# 2DDR3L_16bits.net
KiCad netlist of a schematic drawn in Altium Designer
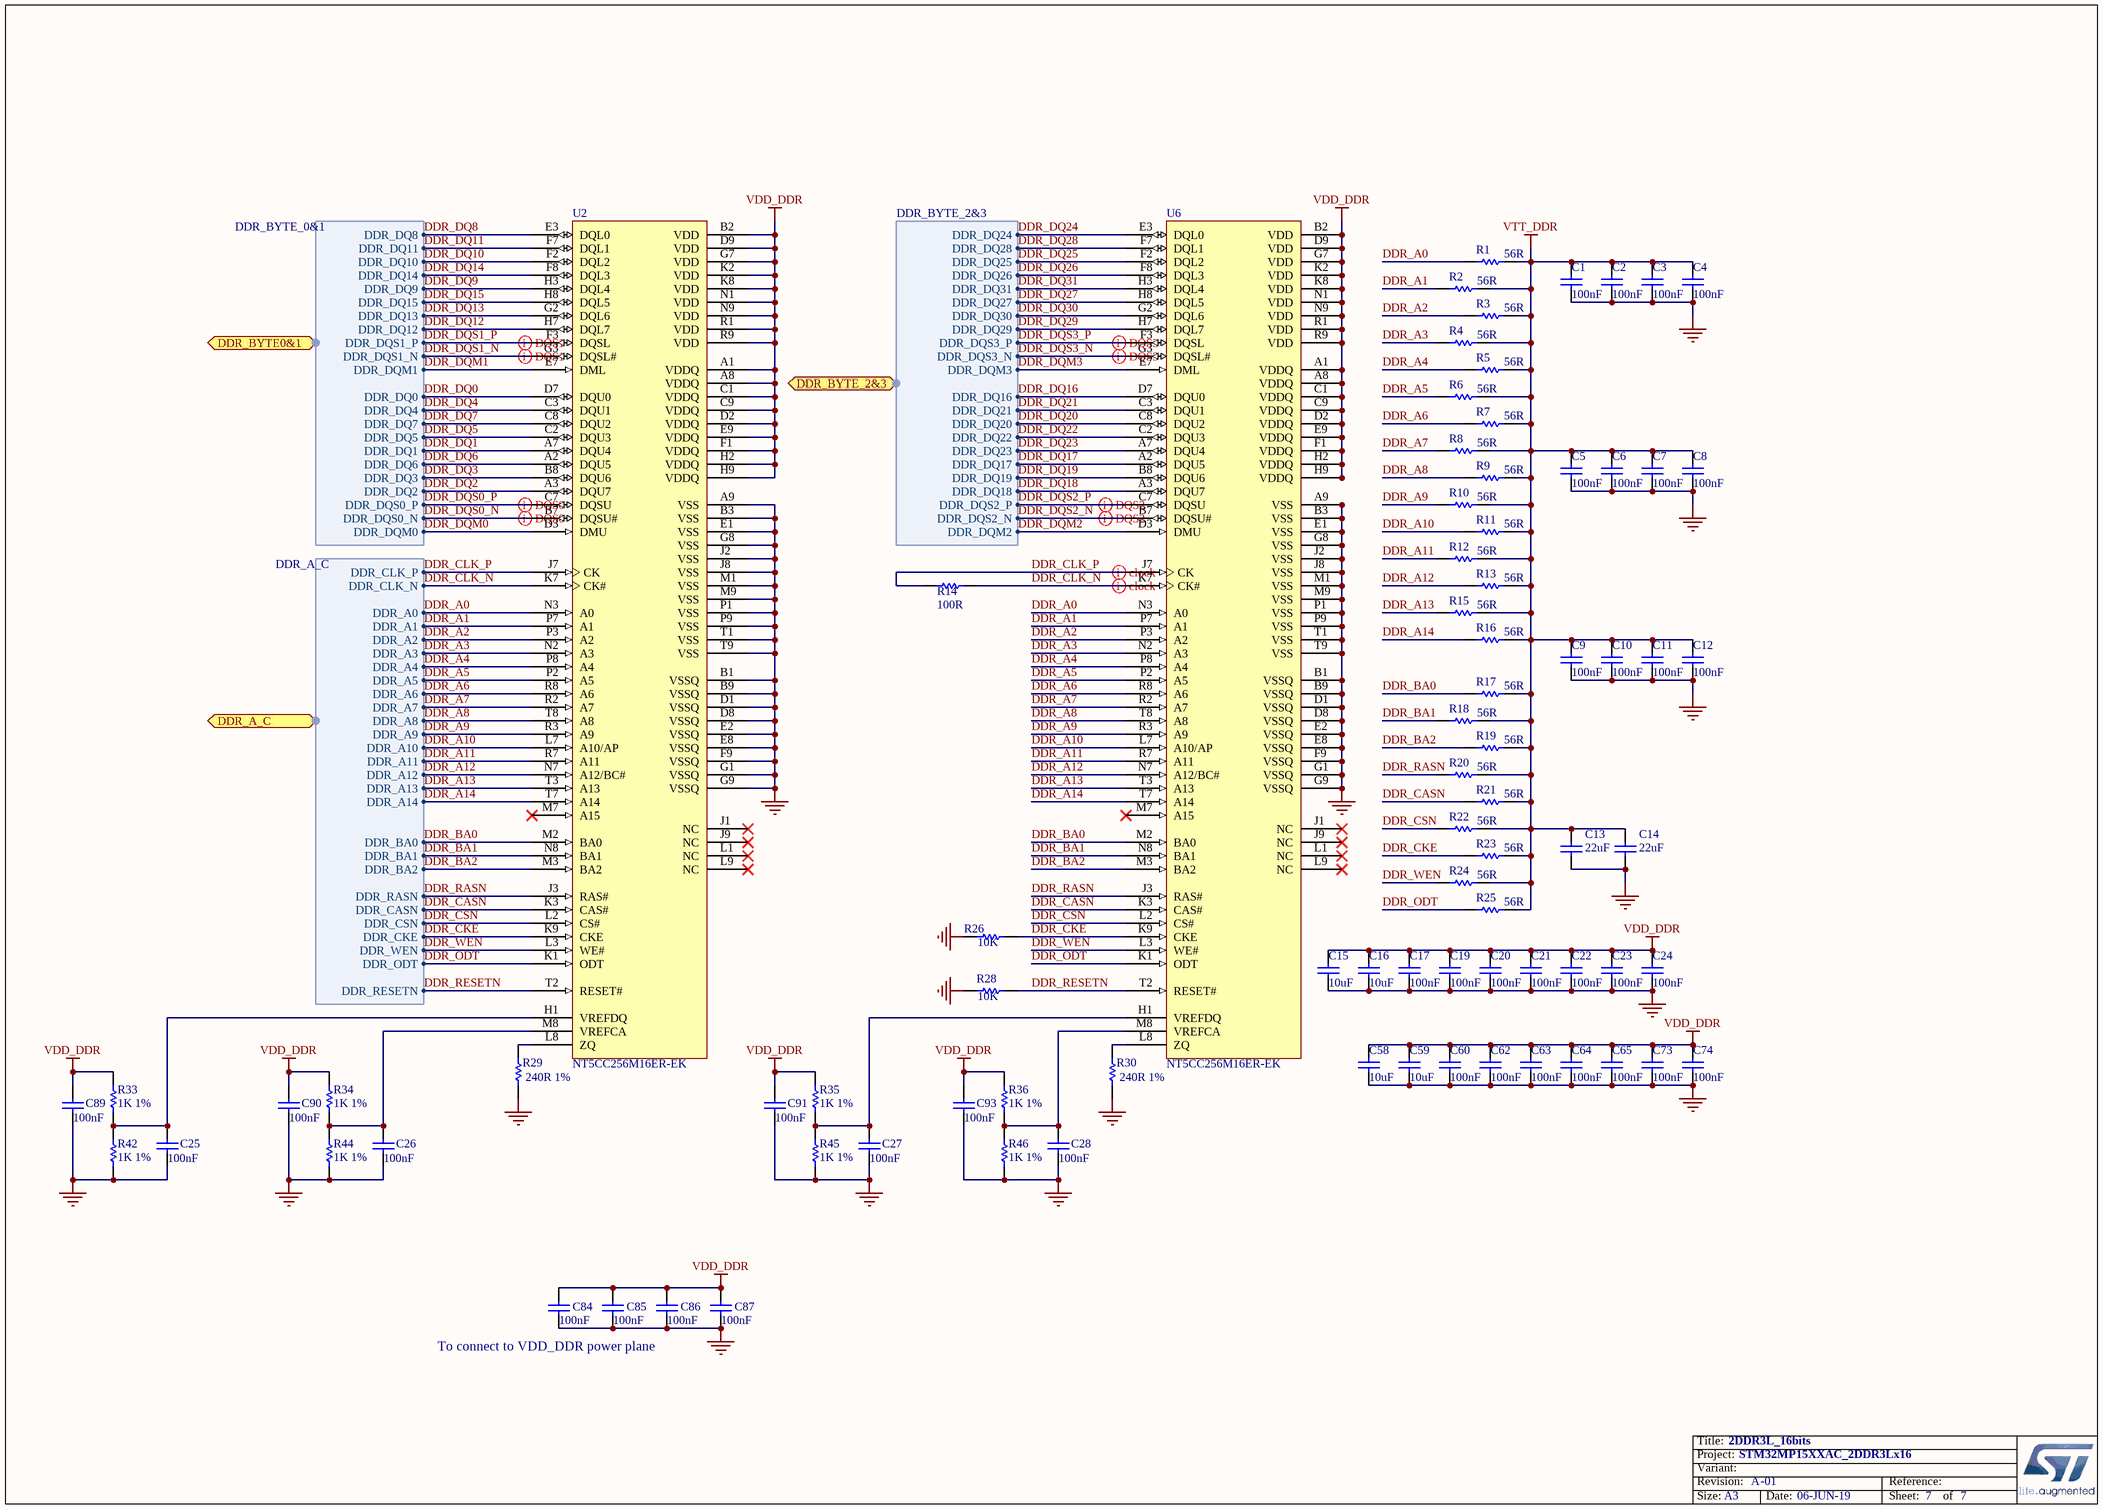
[diagram p0: 2DDR3L_16bits.SchDoc]

(export (version "E")
  (design (tool "Eeschema 10.0.6"))
  (components
    (comp (ref "C1")
      (value "100nF")
      (footprint "C0402")
      (description "Capacitor, MLCC, 100nF, 16V, X7R, 10%, 0402, T=0.5mm")
      (fields
        (field (name "INTERNAL_PART_NUMBER") "MCD-00006")
        (field (name "MANUFACTURER_PART_NUMBER") "CC0402KRX7R7BB104")
        (field (name "PROVIDED_BY") "SUBCO")
      )
      (libsource (lib "MCD_PARTS_database") (part "Capacitor"))
    )
    (comp (ref "C2")
      (value "100nF")
      (footprint "C0402")
      (description "Capacitor, MLCC, 100nF, 16V, X7R, 10%, 0402, T=0.5mm")
      (fields
        (field (name "INTERNAL_PART_NUMBER") "MCD-00006")
        (field (name "MANUFACTURER_PART_NUMBER") "CC0402KRX7R7BB104")
        (field (name "PROVIDED_BY") "SUBCO")
      )
      (libsource (lib "MCD_PARTS_database") (part "Capacitor"))
    )
    (comp (ref "C3")
      (value "100nF")
      (footprint "C0402")
      (description "Capacitor, MLCC, 100nF, 16V, X7R, 10%, 0402, T=0.5mm")
      (fields
        (field (name "INTERNAL_PART_NUMBER") "MCD-00006")
        (field (name "MANUFACTURER_PART_NUMBER") "CC0402KRX7R7BB104")
        (field (name "PROVIDED_BY") "SUBCO")
      )
      (libsource (lib "MCD_PARTS_database") (part "Capacitor"))
    )
    (comp (ref "C4")
      (value "100nF")
      (footprint "C0402")
      (description "Capacitor, MLCC, 100nF, 16V, X7R, 10%, 0402, T=0.5mm")
      (fields
        (field (name "INTERNAL_PART_NUMBER") "MCD-00006")
        (field (name "MANUFACTURER_PART_NUMBER") "CC0402KRX7R7BB104")
        (field (name "PROVIDED_BY") "SUBCO")
      )
      (libsource (lib "MCD_PARTS_database") (part "Capacitor"))
    )
    (comp (ref "C5")
      (value "100nF")
      (footprint "C0402")
      (description "Capacitor, MLCC, 100nF, 16V, X7R, 10%, 0402, T=0.5mm")
      (fields
        (field (name "INTERNAL_PART_NUMBER") "MCD-00006")
        (field (name "MANUFACTURER_PART_NUMBER") "CC0402KRX7R7BB104")
        (field (name "PROVIDED_BY") "SUBCO")
      )
      (libsource (lib "MCD_PARTS_database") (part "Capacitor"))
    )
    (comp (ref "C6")
      (value "100nF")
      (footprint "C0402")
      (description "Capacitor, MLCC, 100nF, 16V, X7R, 10%, 0402, T=0.5mm")
      (fields
        (field (name "INTERNAL_PART_NUMBER") "MCD-00006")
        (field (name "MANUFACTURER_PART_NUMBER") "CC0402KRX7R7BB104")
        (field (name "PROVIDED_BY") "SUBCO")
      )
      (libsource (lib "MCD_PARTS_database") (part "Capacitor"))
    )
    (comp (ref "C7")
      (value "100nF")
      (footprint "C0402")
      (description "Capacitor, MLCC, 100nF, 16V, X7R, 10%, 0402, T=0.5mm")
      (fields
        (field (name "INTERNAL_PART_NUMBER") "MCD-00006")
        (field (name "MANUFACTURER_PART_NUMBER") "CC0402KRX7R7BB104")
        (field (name "PROVIDED_BY") "SUBCO")
      )
      (libsource (lib "MCD_PARTS_database") (part "Capacitor"))
    )
    (comp (ref "C8")
      (value "100nF")
      (footprint "C0402")
      (description "Capacitor, MLCC, 100nF, 16V, X7R, 10%, 0402, T=0.5mm")
      (fields
        (field (name "INTERNAL_PART_NUMBER") "MCD-00006")
        (field (name "MANUFACTURER_PART_NUMBER") "CC0402KRX7R7BB104")
        (field (name "PROVIDED_BY") "SUBCO")
      )
      (libsource (lib "MCD_PARTS_database") (part "Capacitor"))
    )
    (comp (ref "C9")
      (value "100nF")
      (footprint "C0402")
      (description "Capacitor, MLCC, 100nF, 16V, X7R, 10%, 0402, T=0.5mm")
      (fields
        (field (name "INTERNAL_PART_NUMBER") "MCD-00006")
        (field (name "MANUFACTURER_PART_NUMBER") "CC0402KRX7R7BB104")
        (field (name "PROVIDED_BY") "SUBCO")
      )
      (libsource (lib "MCD_PARTS_database") (part "Capacitor"))
    )
    (comp (ref "C10")
      (value "100nF")
      (footprint "C0402")
      (description "Capacitor, MLCC, 100nF, 16V, X7R, 10%, 0402, T=0.5mm")
      (fields
        (field (name "INTERNAL_PART_NUMBER") "MCD-00006")
        (field (name "MANUFACTURER_PART_NUMBER") "CC0402KRX7R7BB104")
        (field (name "PROVIDED_BY") "SUBCO")
      )
      (libsource (lib "MCD_PARTS_database") (part "Capacitor"))
    )
    (comp (ref "C11")
      (value "100nF")
      (footprint "C0402")
      (description "Capacitor, MLCC, 100nF, 16V, X7R, 10%, 0402, T=0.5mm")
      (fields
        (field (name "INTERNAL_PART_NUMBER") "MCD-00006")
        (field (name "MANUFACTURER_PART_NUMBER") "CC0402KRX7R7BB104")
        (field (name "PROVIDED_BY") "SUBCO")
      )
      (libsource (lib "MCD_PARTS_database") (part "Capacitor"))
    )
    (comp (ref "C12")
      (value "100nF")
      (footprint "C0402")
      (description "Capacitor, MLCC, 100nF, 16V, X7R, 10%, 0402, T=0.5mm")
      (fields
        (field (name "INTERNAL_PART_NUMBER") "MCD-00006")
        (field (name "MANUFACTURER_PART_NUMBER") "CC0402KRX7R7BB104")
        (field (name "PROVIDED_BY") "SUBCO")
      )
      (libsource (lib "MCD_PARTS_database") (part "Capacitor"))
    )
    (comp (ref "C13")
      (value "22uF")
      (footprint "C0603")
      (description "Capacitor, MLCC, 22uF, 6V3, X5R, 20%, 0603, T=0,8mm")
      (fields
        (field (name "INTERNAL_PART_NUMBER") "MCD-00100")
        (field (name "MANUFACTURER_PART_NUMBER") "GRM188R60J226MEA0J")
        (field (name "PROVIDED_BY") "SUBCO")
      )
      (libsource (lib "MCD_PARTS_database") (part "Capacitor"))
    )
    (comp (ref "C14")
      (value "22uF")
      (footprint "C0603")
      (description "Capacitor, MLCC, 22uF, 6V3, X5R, 20%, 0603, T=0,8mm")
      (fields
        (field (name "INTERNAL_PART_NUMBER") "MCD-00100")
        (field (name "MANUFACTURER_PART_NUMBER") "GRM188R60J226MEA0J")
        (field (name "PROVIDED_BY") "SUBCO")
      )
      (libsource (lib "MCD_PARTS_database") (part "Capacitor"))
    )
    (comp (ref "C15")
      (value "10uF")
      (footprint "C0603")
      (description "Capacitor, MLCC, 10µF, 10V, X5R, 10%, 0603, T=0.8mm")
      (fields
        (field (name "INTERNAL_PART_NUMBER") "MCD-01124")
        (field (name "MANUFACTURER_PART_NUMBER") "GRM188R61A106KAAL")
        (field (name "PROVIDED_BY") "SUBCO")
      )
      (libsource (lib "MCD_PARTS_database") (part "Capacitor"))
    )
    (comp (ref "C16")
      (value "10uF")
      (footprint "C0603")
      (description "Capacitor, MLCC, 10µF, 10V, X5R, 10%, 0603, T=0.8mm")
      (fields
        (field (name "INTERNAL_PART_NUMBER") "MCD-01124")
        (field (name "MANUFACTURER_PART_NUMBER") "GRM188R61A106KAAL")
        (field (name "PROVIDED_BY") "SUBCO")
      )
      (libsource (lib "MCD_PARTS_database") (part "Capacitor"))
    )
    (comp (ref "C17")
      (value "100nF")
      (footprint "C0402")
      (description "Capacitor, MLCC, 100nF, 16V, X7R, 10%, 0402, T=0.5mm")
      (fields
        (field (name "INTERNAL_PART_NUMBER") "MCD-00006")
        (field (name "MANUFACTURER_PART_NUMBER") "CC0402KRX7R7BB104")
        (field (name "PROVIDED_BY") "SUBCO")
      )
      (libsource (lib "MCD_PARTS_database") (part "Capacitor"))
    )
    (comp (ref "C19")
      (value "100nF")
      (footprint "C0402")
      (description "Capacitor, MLCC, 100nF, 16V, X7R, 10%, 0402, T=0.5mm")
      (fields
        (field (name "INTERNAL_PART_NUMBER") "MCD-00006")
        (field (name "MANUFACTURER_PART_NUMBER") "CC0402KRX7R7BB104")
        (field (name "PROVIDED_BY") "SUBCO")
      )
      (libsource (lib "MCD_PARTS_database") (part "Capacitor"))
    )
    (comp (ref "C20")
      (value "100nF")
      (footprint "C0402")
      (description "Capacitor, MLCC, 100nF, 16V, X7R, 10%, 0402, T=0.5mm")
      (fields
        (field (name "INTERNAL_PART_NUMBER") "MCD-00006")
        (field (name "MANUFACTURER_PART_NUMBER") "CC0402KRX7R7BB104")
        (field (name "PROVIDED_BY") "SUBCO")
      )
      (libsource (lib "MCD_PARTS_database") (part "Capacitor"))
    )
    (comp (ref "C21")
      (value "100nF")
      (footprint "C0402")
      (description "Capacitor, MLCC, 100nF, 16V, X7R, 10%, 0402, T=0.5mm")
      (fields
        (field (name "INTERNAL_PART_NUMBER") "MCD-00006")
        (field (name "MANUFACTURER_PART_NUMBER") "CC0402KRX7R7BB104")
        (field (name "PROVIDED_BY") "SUBCO")
      )
      (libsource (lib "MCD_PARTS_database") (part "Capacitor"))
    )
    (comp (ref "C22")
      (value "100nF")
      (footprint "C0402")
      (description "Capacitor, MLCC, 100nF, 16V, X7R, 10%, 0402, T=0.5mm")
      (fields
        (field (name "INTERNAL_PART_NUMBER") "MCD-00006")
        (field (name "MANUFACTURER_PART_NUMBER") "CC0402KRX7R7BB104")
        (field (name "PROVIDED_BY") "SUBCO")
      )
      (libsource (lib "MCD_PARTS_database") (part "Capacitor"))
    )
    (comp (ref "C23")
      (value "100nF")
      (footprint "C0402")
      (description "Capacitor, MLCC, 100nF, 16V, X7R, 10%, 0402, T=0.5mm")
      (fields
        (field (name "INTERNAL_PART_NUMBER") "MCD-00006")
        (field (name "MANUFACTURER_PART_NUMBER") "CC0402KRX7R7BB104")
        (field (name "PROVIDED_BY") "SUBCO")
      )
      (libsource (lib "MCD_PARTS_database") (part "Capacitor"))
    )
    (comp (ref "C24")
      (value "100nF")
      (footprint "C0402")
      (description "Capacitor, MLCC, 100nF, 16V, X7R, 10%, 0402, T=0.5mm")
      (fields
        (field (name "INTERNAL_PART_NUMBER") "MCD-00006")
        (field (name "MANUFACTURER_PART_NUMBER") "CC0402KRX7R7BB104")
        (field (name "PROVIDED_BY") "SUBCO")
      )
      (libsource (lib "MCD_PARTS_database") (part "Capacitor"))
    )
    (comp (ref "C25")
      (value "100nF")
      (footprint "C0402")
      (description "Capacitor, MLCC, 100nF, 16V, X7R, 10%, 0402, T=0.5mm")
      (fields
        (field (name "INTERNAL_PART_NUMBER") "MCD-00006")
        (field (name "MANUFACTURER_PART_NUMBER") "CC0402KRX7R7BB104")
        (field (name "PROVIDED_BY") "SUBCO")
      )
      (libsource (lib "MCD_PARTS_database") (part "Capacitor"))
    )
    (comp (ref "C26")
      (value "100nF")
      (footprint "C0402")
      (description "Capacitor, MLCC, 100nF, 16V, X7R, 10%, 0402, T=0.5mm")
      (fields
        (field (name "INTERNAL_PART_NUMBER") "MCD-00006")
        (field (name "MANUFACTURER_PART_NUMBER") "CC0402KRX7R7BB104")
        (field (name "PROVIDED_BY") "SUBCO")
      )
      (libsource (lib "MCD_PARTS_database") (part "Capacitor"))
    )
    (comp (ref "C27")
      (value "100nF")
      (footprint "C0402")
      (description "Capacitor, MLCC, 100nF, 16V, X7R, 10%, 0402, T=0.5mm")
      (fields
        (field (name "INTERNAL_PART_NUMBER") "MCD-00006")
        (field (name "MANUFACTURER_PART_NUMBER") "CC0402KRX7R7BB104")
        (field (name "PROVIDED_BY") "SUBCO")
      )
      (libsource (lib "MCD_PARTS_database") (part "Capacitor"))
    )
    (comp (ref "C28")
      (value "100nF")
      (footprint "C0402")
      (description "Capacitor, MLCC, 100nF, 16V, X7R, 10%, 0402, T=0.5mm")
      (fields
        (field (name "INTERNAL_PART_NUMBER") "MCD-00006")
        (field (name "MANUFACTURER_PART_NUMBER") "CC0402KRX7R7BB104")
        (field (name "PROVIDED_BY") "SUBCO")
      )
      (libsource (lib "MCD_PARTS_database") (part "Capacitor"))
    )
    (comp (ref "C58")
      (value "10uF")
      (footprint "C0603")
      (description "Capacitor, MLCC, 10µF, 10V, X5R, 10%, 0603, T=0.8mm")
      (fields
        (field (name "INTERNAL_PART_NUMBER") "MCD-01124")
        (field (name "MANUFACTURER_PART_NUMBER") "GRM188R61A106KAAL")
        (field (name "PROVIDED_BY") "SUBCO")
      )
      (libsource (lib "MCD_PARTS_database") (part "Capacitor"))
    )
    (comp (ref "C59")
      (value "10uF")
      (footprint "C0603")
      (description "Capacitor, MLCC, 10µF, 10V, X5R, 10%, 0603, T=0.8mm")
      (fields
        (field (name "INTERNAL_PART_NUMBER") "MCD-01124")
        (field (name "MANUFACTURER_PART_NUMBER") "GRM188R61A106KAAL")
        (field (name "PROVIDED_BY") "SUBCO")
      )
      (libsource (lib "MCD_PARTS_database") (part "Capacitor"))
    )
    (comp (ref "C60")
      (value "100nF")
      (footprint "C0402")
      (description "Capacitor, MLCC, 100nF, 16V, X7R, 10%, 0402, T=0.5mm")
      (fields
        (field (name "INTERNAL_PART_NUMBER") "MCD-00006")
        (field (name "MANUFACTURER_PART_NUMBER") "CC0402KRX7R7BB104")
        (field (name "PROVIDED_BY") "SUBCO")
      )
      (libsource (lib "MCD_PARTS_database") (part "Capacitor"))
    )
    (comp (ref "C62")
      (value "100nF")
      (footprint "C0402")
      (description "Capacitor, MLCC, 100nF, 16V, X7R, 10%, 0402, T=0.5mm")
      (fields
        (field (name "INTERNAL_PART_NUMBER") "MCD-00006")
        (field (name "MANUFACTURER_PART_NUMBER") "CC0402KRX7R7BB104")
        (field (name "PROVIDED_BY") "SUBCO")
      )
      (libsource (lib "MCD_PARTS_database") (part "Capacitor"))
    )
    (comp (ref "C63")
      (value "100nF")
      (footprint "C0402")
      (description "Capacitor, MLCC, 100nF, 16V, X7R, 10%, 0402, T=0.5mm")
      (fields
        (field (name "INTERNAL_PART_NUMBER") "MCD-00006")
        (field (name "MANUFACTURER_PART_NUMBER") "CC0402KRX7R7BB104")
        (field (name "PROVIDED_BY") "SUBCO")
      )
      (libsource (lib "MCD_PARTS_database") (part "Capacitor"))
    )
    (comp (ref "C64")
      (value "100nF")
      (footprint "C0402")
      (description "Capacitor, MLCC, 100nF, 16V, X7R, 10%, 0402, T=0.5mm")
      (fields
        (field (name "INTERNAL_PART_NUMBER") "MCD-00006")
        (field (name "MANUFACTURER_PART_NUMBER") "CC0402KRX7R7BB104")
        (field (name "PROVIDED_BY") "SUBCO")
      )
      (libsource (lib "MCD_PARTS_database") (part "Capacitor"))
    )
    (comp (ref "C65")
      (value "100nF")
      (footprint "C0402")
      (description "Capacitor, MLCC, 100nF, 16V, X7R, 10%, 0402, T=0.5mm")
      (fields
        (field (name "INTERNAL_PART_NUMBER") "MCD-00006")
        (field (name "MANUFACTURER_PART_NUMBER") "CC0402KRX7R7BB104")
        (field (name "PROVIDED_BY") "SUBCO")
      )
      (libsource (lib "MCD_PARTS_database") (part "Capacitor"))
    )
    (comp (ref "C73")
      (value "100nF")
      (footprint "C0402")
      (description "Capacitor, MLCC, 100nF, 16V, X7R, 10%, 0402, T=0.5mm")
      (fields
        (field (name "INTERNAL_PART_NUMBER") "MCD-00006")
        (field (name "MANUFACTURER_PART_NUMBER") "CC0402KRX7R7BB104")
        (field (name "PROVIDED_BY") "SUBCO")
      )
      (libsource (lib "MCD_PARTS_database") (part "Capacitor"))
    )
    (comp (ref "C74")
      (value "100nF")
      (footprint "C0402")
      (description "Capacitor, MLCC, 100nF, 16V, X7R, 10%, 0402, T=0.5mm")
      (fields
        (field (name "INTERNAL_PART_NUMBER") "MCD-00006")
        (field (name "MANUFACTURER_PART_NUMBER") "CC0402KRX7R7BB104")
        (field (name "PROVIDED_BY") "SUBCO")
      )
      (libsource (lib "MCD_PARTS_database") (part "Capacitor"))
    )
    (comp (ref "C84")
      (value "100nF")
      (footprint "C0402")
      (description "Capacitor, MLCC, 100nF, 16V, X7R, 10%, 0402, T=0.5mm")
      (fields
        (field (name "INTERNAL_PART_NUMBER") "MCD-00006")
        (field (name "MANUFACTURER_PART_NUMBER") "CC0402KRX7R7BB104")
        (field (name "PROVIDED_BY") "SUBCO")
      )
      (libsource (lib "MCD_PARTS_database") (part "Capacitor"))
    )
    (comp (ref "C85")
      (value "100nF")
      (footprint "C0402")
      (description "Capacitor, MLCC, 100nF, 16V, X7R, 10%, 0402, T=0.5mm")
      (fields
        (field (name "INTERNAL_PART_NUMBER") "MCD-00006")
        (field (name "MANUFACTURER_PART_NUMBER") "CC0402KRX7R7BB104")
        (field (name "PROVIDED_BY") "SUBCO")
      )
      (libsource (lib "MCD_PARTS_database") (part "Capacitor"))
    )
    (comp (ref "C86")
      (value "100nF")
      (footprint "C0402")
      (description "Capacitor, MLCC, 100nF, 16V, X7R, 10%, 0402, T=0.5mm")
      (fields
        (field (name "INTERNAL_PART_NUMBER") "MCD-00006")
        (field (name "MANUFACTURER_PART_NUMBER") "CC0402KRX7R7BB104")
        (field (name "PROVIDED_BY") "SUBCO")
      )
      (libsource (lib "MCD_PARTS_database") (part "Capacitor"))
    )
    (comp (ref "C87")
      (value "100nF")
      (footprint "C0402")
      (description "Capacitor, MLCC, 100nF, 16V, X7R, 10%, 0402, T=0.5mm")
      (fields
        (field (name "INTERNAL_PART_NUMBER") "MCD-00006")
        (field (name "MANUFACTURER_PART_NUMBER") "CC0402KRX7R7BB104")
        (field (name "PROVIDED_BY") "SUBCO")
      )
      (libsource (lib "MCD_PARTS_database") (part "Capacitor"))
    )
    (comp (ref "C89")
      (value "100nF")
      (footprint "C0402")
      (description "Capacitor, MLCC, 100nF, 16V, X7R, 10%, 0402, T=0.5mm")
      (fields
        (field (name "INTERNAL_PART_NUMBER") "MCD-00006")
        (field (name "MANUFACTURER_PART_NUMBER") "CC0402KRX7R7BB104")
        (field (name "PROVIDED_BY") "SUBCO")
      )
      (libsource (lib "MCD_PARTS_database") (part "Capacitor"))
    )
    (comp (ref "C90")
      (value "100nF")
      (footprint "C0402")
      (description "Capacitor, MLCC, 100nF, 16V, X7R, 10%, 0402, T=0.5mm")
      (fields
        (field (name "INTERNAL_PART_NUMBER") "MCD-00006")
        (field (name "MANUFACTURER_PART_NUMBER") "CC0402KRX7R7BB104")
        (field (name "PROVIDED_BY") "SUBCO")
      )
      (libsource (lib "MCD_PARTS_database") (part "Capacitor"))
    )
    (comp (ref "C91")
      (value "100nF")
      (footprint "C0402")
      (description "Capacitor, MLCC, 100nF, 16V, X7R, 10%, 0402, T=0.5mm")
      (fields
        (field (name "INTERNAL_PART_NUMBER") "MCD-00006")
        (field (name "MANUFACTURER_PART_NUMBER") "CC0402KRX7R7BB104")
        (field (name "PROVIDED_BY") "SUBCO")
      )
      (libsource (lib "MCD_PARTS_database") (part "Capacitor"))
    )
    (comp (ref "C93")
      (value "100nF")
      (footprint "C0402")
      (description "Capacitor, MLCC, 100nF, 16V, X7R, 10%, 0402, T=0.5mm")
      (fields
        (field (name "INTERNAL_PART_NUMBER") "MCD-00006")
        (field (name "MANUFACTURER_PART_NUMBER") "CC0402KRX7R7BB104")
        (field (name "PROVIDED_BY") "SUBCO")
      )
      (libsource (lib "MCD_PARTS_database") (part "Capacitor"))
    )
    (comp (ref "R1")
      (value "56R")
      (footprint "R0402")
      (description "Resistor,56R,0402,1%,1/16W")
      (fields
        (field (name "INTERNAL_PART_NUMBER") "MCD-00054")
        (field (name "MANUFACTURER_PART_NUMBER") "RC0402FR-0756RL")
        (field (name "PROVIDED_BY") "SUBCO")
      )
      (libsource (lib "MCD_PARTS_database") (part "Resistor"))
    )
    (comp (ref "R2")
      (value "56R")
      (footprint "R0402")
      (description "Resistor,56R,0402,1%,1/16W")
      (fields
        (field (name "INTERNAL_PART_NUMBER") "MCD-00054")
        (field (name "MANUFACTURER_PART_NUMBER") "RC0402FR-0756RL")
        (field (name "PROVIDED_BY") "SUBCO")
      )
      (libsource (lib "MCD_PARTS_database") (part "Resistor"))
    )
    (comp (ref "R3")
      (value "56R")
      (footprint "R0402")
      (description "Resistor,56R,0402,1%,1/16W")
      (fields
        (field (name "INTERNAL_PART_NUMBER") "MCD-00054")
        (field (name "MANUFACTURER_PART_NUMBER") "RC0402FR-0756RL")
        (field (name "PROVIDED_BY") "SUBCO")
      )
      (libsource (lib "MCD_PARTS_database") (part "Resistor"))
    )
    (comp (ref "R4")
      (value "56R")
      (footprint "R0402")
      (description "Resistor,56R,0402,1%,1/16W")
      (fields
        (field (name "INTERNAL_PART_NUMBER") "MCD-00054")
        (field (name "MANUFACTURER_PART_NUMBER") "RC0402FR-0756RL")
        (field (name "PROVIDED_BY") "SUBCO")
      )
      (libsource (lib "MCD_PARTS_database") (part "Resistor"))
    )
    (comp (ref "R5")
      (value "56R")
      (footprint "R0402")
      (description "Resistor,56R,0402,1%,1/16W")
      (fields
        (field (name "INTERNAL_PART_NUMBER") "MCD-00054")
        (field (name "MANUFACTURER_PART_NUMBER") "RC0402FR-0756RL")
        (field (name "PROVIDED_BY") "SUBCO")
      )
      (libsource (lib "MCD_PARTS_database") (part "Resistor"))
    )
    (comp (ref "R6")
      (value "56R")
      (footprint "R0402")
      (description "Resistor,56R,0402,1%,1/16W")
      (fields
        (field (name "INTERNAL_PART_NUMBER") "MCD-00054")
        (field (name "MANUFACTURER_PART_NUMBER") "RC0402FR-0756RL")
        (field (name "PROVIDED_BY") "SUBCO")
      )
      (libsource (lib "MCD_PARTS_database") (part "Resistor"))
    )
    (comp (ref "R7")
      (value "56R")
      (footprint "R0402")
      (description "Resistor,56R,0402,1%,1/16W")
      (fields
        (field (name "INTERNAL_PART_NUMBER") "MCD-00054")
        (field (name "MANUFACTURER_PART_NUMBER") "RC0402FR-0756RL")
        (field (name "PROVIDED_BY") "SUBCO")
      )
      (libsource (lib "MCD_PARTS_database") (part "Resistor"))
    )
    (comp (ref "R8")
      (value "56R")
      (footprint "R0402")
      (description "Resistor,56R,0402,1%,1/16W")
      (fields
        (field (name "INTERNAL_PART_NUMBER") "MCD-00054")
        (field (name "MANUFACTURER_PART_NUMBER") "RC0402FR-0756RL")
        (field (name "PROVIDED_BY") "SUBCO")
      )
      (libsource (lib "MCD_PARTS_database") (part "Resistor"))
    )
    (comp (ref "R9")
      (value "56R")
      (footprint "R0402")
      (description "Resistor,56R,0402,1%,1/16W")
      (fields
        (field (name "INTERNAL_PART_NUMBER") "MCD-00054")
        (field (name "MANUFACTURER_PART_NUMBER") "RC0402FR-0756RL")
        (field (name "PROVIDED_BY") "SUBCO")
      )
      (libsource (lib "MCD_PARTS_database") (part "Resistor"))
    )
    (comp (ref "R10")
      (value "56R")
      (footprint "R0402")
      (description "Resistor,56R,0402,1%,1/16W")
      (fields
        (field (name "INTERNAL_PART_NUMBER") "MCD-00054")
        (field (name "MANUFACTURER_PART_NUMBER") "RC0402FR-0756RL")
        (field (name "PROVIDED_BY") "SUBCO")
      )
      (libsource (lib "MCD_PARTS_database") (part "Resistor"))
    )
    (comp (ref "R11")
      (value "56R")
      (footprint "R0402")
      (description "Resistor,56R,0402,1%,1/16W")
      (fields
        (field (name "INTERNAL_PART_NUMBER") "MCD-00054")
        (field (name "MANUFACTURER_PART_NUMBER") "RC0402FR-0756RL")
        (field (name "PROVIDED_BY") "SUBCO")
      )
      (libsource (lib "MCD_PARTS_database") (part "Resistor"))
    )
    (comp (ref "R12")
      (value "56R")
      (footprint "R0402")
      (description "Resistor,56R,0402,1%,1/16W")
      (fields
        (field (name "INTERNAL_PART_NUMBER") "MCD-00054")
        (field (name "MANUFACTURER_PART_NUMBER") "RC0402FR-0756RL")
        (field (name "PROVIDED_BY") "SUBCO")
      )
      (libsource (lib "MCD_PARTS_database") (part "Resistor"))
    )
    (comp (ref "R13")
      (value "56R")
      (footprint "R0402")
      (description "Resistor,56R,0402,1%,1/16W")
      (fields
        (field (name "INTERNAL_PART_NUMBER") "MCD-00054")
        (field (name "MANUFACTURER_PART_NUMBER") "RC0402FR-0756RL")
        (field (name "PROVIDED_BY") "SUBCO")
      )
      (libsource (lib "MCD_PARTS_database") (part "Resistor"))
    )
    (comp (ref "R14")
      (value "100R")
      (footprint "R0402")
      (description "Resistor,100R,0402,1%,1/16W")
      (fields
        (field (name "INTERNAL_PART_NUMBER") "MCD-00067")
        (field (name "MANUFACTURER_PART_NUMBER") "RC0402FR-07100RL")
        (field (name "PROVIDED_BY") "SUBCO")
      )
      (libsource (lib "MCD_PARTS_database") (part "Resistor"))
    )
    (comp (ref "R15")
      (value "56R")
      (footprint "R0402")
      (description "Resistor,56R,0402,1%,1/16W")
      (fields
        (field (name "INTERNAL_PART_NUMBER") "MCD-00054")
        (field (name "MANUFACTURER_PART_NUMBER") "RC0402FR-0756RL")
        (field (name "PROVIDED_BY") "SUBCO")
      )
      (libsource (lib "MCD_PARTS_database") (part "Resistor"))
    )
    (comp (ref "R16")
      (value "56R")
      (footprint "R0402")
      (description "Resistor,56R,0402,1%,1/16W")
      (fields
        (field (name "INTERNAL_PART_NUMBER") "MCD-00054")
        (field (name "MANUFACTURER_PART_NUMBER") "RC0402FR-0756RL")
        (field (name "PROVIDED_BY") "SUBCO")
      )
      (libsource (lib "MCD_PARTS_database") (part "Resistor"))
    )
    (comp (ref "R17")
      (value "56R")
      (footprint "R0402")
      (description "Resistor,56R,0402,1%,1/16W")
      (fields
        (field (name "INTERNAL_PART_NUMBER") "MCD-00054")
        (field (name "MANUFACTURER_PART_NUMBER") "RC0402FR-0756RL")
        (field (name "PROVIDED_BY") "SUBCO")
      )
      (libsource (lib "MCD_PARTS_database") (part "Resistor"))
    )
    (comp (ref "R18")
      (value "56R")
      (footprint "R0402")
      (description "Resistor,56R,0402,1%,1/16W")
      (fields
        (field (name "INTERNAL_PART_NUMBER") "MCD-00054")
        (field (name "MANUFACTURER_PART_NUMBER") "RC0402FR-0756RL")
        (field (name "PROVIDED_BY") "SUBCO")
      )
      (libsource (lib "MCD_PARTS_database") (part "Resistor"))
    )
    (comp (ref "R19")
      (value "56R")
      (footprint "R0402")
      (description "Resistor,56R,0402,1%,1/16W")
      (fields
        (field (name "INTERNAL_PART_NUMBER") "MCD-00054")
        (field (name "MANUFACTURER_PART_NUMBER") "RC0402FR-0756RL")
        (field (name "PROVIDED_BY") "SUBCO")
      )
      (libsource (lib "MCD_PARTS_database") (part "Resistor"))
    )
    (comp (ref "R20")
      (value "56R")
      (footprint "R0402")
      (description "Resistor,56R,0402,1%,1/16W")
      (fields
        (field (name "INTERNAL_PART_NUMBER") "MCD-00054")
        (field (name "MANUFACTURER_PART_NUMBER") "RC0402FR-0756RL")
        (field (name "PROVIDED_BY") "SUBCO")
      )
      (libsource (lib "MCD_PARTS_database") (part "Resistor"))
    )
    (comp (ref "R21")
      (value "56R")
      (footprint "R0402")
      (description "Resistor,56R,0402,1%,1/16W")
      (fields
        (field (name "INTERNAL_PART_NUMBER") "MCD-00054")
        (field (name "MANUFACTURER_PART_NUMBER") "RC0402FR-0756RL")
        (field (name "PROVIDED_BY") "SUBCO")
      )
      (libsource (lib "MCD_PARTS_database") (part "Resistor"))
    )
    (comp (ref "R22")
      (value "56R")
      (footprint "R0402")
      (description "Resistor,56R,0402,1%,1/16W")
      (fields
        (field (name "INTERNAL_PART_NUMBER") "MCD-00054")
        (field (name "MANUFACTURER_PART_NUMBER") "RC0402FR-0756RL")
        (field (name "PROVIDED_BY") "SUBCO")
      )
      (libsource (lib "MCD_PARTS_database") (part "Resistor"))
    )
    (comp (ref "R23")
      (value "56R")
      (footprint "R0402")
      (description "Resistor,56R,0402,1%,1/16W")
      (fields
        (field (name "INTERNAL_PART_NUMBER") "MCD-00054")
        (field (name "MANUFACTURER_PART_NUMBER") "RC0402FR-0756RL")
        (field (name "PROVIDED_BY") "SUBCO")
      )
      (libsource (lib "MCD_PARTS_database") (part "Resistor"))
    )
    (comp (ref "R24")
      (value "56R")
      (footprint "R0402")
      (description "Resistor,56R,0402,1%,1/16W")
      (fields
        (field (name "INTERNAL_PART_NUMBER") "MCD-00054")
        (field (name "MANUFACTURER_PART_NUMBER") "RC0402FR-0756RL")
        (field (name "PROVIDED_BY") "SUBCO")
      )
      (libsource (lib "MCD_PARTS_database") (part "Resistor"))
    )
    (comp (ref "R25")
      (value "56R")
      (footprint "R0402")
      (description "Resistor,56R,0402,1%,1/16W")
      (fields
        (field (name "INTERNAL_PART_NUMBER") "MCD-00054")
        (field (name "MANUFACTURER_PART_NUMBER") "RC0402FR-0756RL")
        (field (name "PROVIDED_BY") "SUBCO")
      )
      (libsource (lib "MCD_PARTS_database") (part "Resistor"))
    )
    (comp (ref "R26")
      (value "10K")
      (footprint "R0402")
      (description "Resistor,10K,0402,1%,1/16W")
      (fields
        (field (name "INTERNAL_PART_NUMBER") "MCD-00053")
        (field (name "MANUFACTURER_PART_NUMBER") "RC0402FR-0710KL")
        (field (name "PROVIDED_BY") "SUBCO")
      )
      (libsource (lib "MCD_PARTS_database") (part "Resistor"))
    )
    (comp (ref "R28")
      (value "10K")
      (footprint "R0402")
      (description "Resistor,10K,0402,1%,1/16W")
      (fields
        (field (name "INTERNAL_PART_NUMBER") "MCD-00053")
        (field (name "MANUFACTURER_PART_NUMBER") "RC0402FR-0710KL")
        (field (name "PROVIDED_BY") "SUBCO")
      )
      (libsource (lib "MCD_PARTS_database") (part "Resistor"))
    )
    (comp (ref "R29")
      (value "240R 1%")
      (footprint "R0402")
      (description "Resistor,240R,0402,1%,1/16W")
      (fields
        (field (name "INTERNAL_PART_NUMBER") "MCD-00120")
        (field (name "MANUFACTURER_PART_NUMBER") "RC0402FR-07240RL")
        (field (name "PROVIDED_BY") "SUBCO")
      )
      (libsource (lib "MCD_PARTS_database") (part "Resistor"))
    )
    (comp (ref "R30")
      (value "240R 1%")
      (footprint "R0402")
      (description "Resistor,240R,0402,1%,1/16W")
      (fields
        (field (name "INTERNAL_PART_NUMBER") "MCD-00120")
        (field (name "MANUFACTURER_PART_NUMBER") "RC0402FR-07240RL")
        (field (name "PROVIDED_BY") "SUBCO")
      )
      (libsource (lib "MCD_PARTS_database") (part "Resistor"))
    )
    (comp (ref "R33")
      (value "1K 1%")
      (footprint "R0402")
      (description "Resistor,1K,0402,1%,1/16W")
      (fields
        (field (name "INTERNAL_PART_NUMBER") "MCD-00061")
        (field (name "MANUFACTURER_PART_NUMBER") "RC0402FR-071KL")
        (field (name "PROVIDED_BY") "SUBCO")
      )
      (libsource (lib "MCD_PARTS_database") (part "Resistor"))
    )
    (comp (ref "R34")
      (value "1K 1%")
      (footprint "R0402")
      (description "Resistor,1K,0402,1%,1/16W")
      (fields
        (field (name "INTERNAL_PART_NUMBER") "MCD-00061")
        (field (name "MANUFACTURER_PART_NUMBER") "RC0402FR-071KL")
        (field (name "PROVIDED_BY") "SUBCO")
      )
      (libsource (lib "MCD_PARTS_database") (part "Resistor"))
    )
    (comp (ref "R35")
      (value "1K 1%")
      (footprint "R0402")
      (description "Resistor,1K,0402,1%,1/16W")
      (fields
        (field (name "INTERNAL_PART_NUMBER") "MCD-00061")
        (field (name "MANUFACTURER_PART_NUMBER") "RC0402FR-071KL")
        (field (name "PROVIDED_BY") "SUBCO")
      )
      (libsource (lib "MCD_PARTS_database") (part "Resistor"))
    )
    (comp (ref "R36")
      (value "1K 1%")
      (footprint "R0402")
      (description "Resistor,1K,0402,1%,1/16W")
      (fields
        (field (name "INTERNAL_PART_NUMBER") "MCD-00061")
        (field (name "MANUFACTURER_PART_NUMBER") "RC0402FR-071KL")
        (field (name "PROVIDED_BY") "SUBCO")
      )
      (libsource (lib "MCD_PARTS_database") (part "Resistor"))
    )
    (comp (ref "R42")
      (value "1K 1%")
      (footprint "R0402")
      (description "Resistor,1K,0402,1%,1/16W")
      (fields
        (field (name "INTERNAL_PART_NUMBER") "MCD-00061")
        (field (name "MANUFACTURER_PART_NUMBER") "RC0402FR-071KL")
        (field (name "PROVIDED_BY") "SUBCO")
      )
      (libsource (lib "MCD_PARTS_database") (part "Resistor"))
    )
    (comp (ref "R44")
      (value "1K 1%")
      (footprint "R0402")
      (description "Resistor,1K,0402,1%,1/16W")
      (fields
        (field (name "INTERNAL_PART_NUMBER") "MCD-00061")
        (field (name "MANUFACTURER_PART_NUMBER") "RC0402FR-071KL")
        (field (name "PROVIDED_BY") "SUBCO")
      )
      (libsource (lib "MCD_PARTS_database") (part "Resistor"))
    )
    (comp (ref "R45")
      (value "1K 1%")
      (footprint "R0402")
      (description "Resistor,1K,0402,1%,1/16W")
      (fields
        (field (name "INTERNAL_PART_NUMBER") "MCD-00061")
        (field (name "MANUFACTURER_PART_NUMBER") "RC0402FR-071KL")
        (field (name "PROVIDED_BY") "SUBCO")
      )
      (libsource (lib "MCD_PARTS_database") (part "Resistor"))
    )
    (comp (ref "R46")
      (value "1K 1%")
      (footprint "R0402")
      (description "Resistor,1K,0402,1%,1/16W")
      (fields
        (field (name "INTERNAL_PART_NUMBER") "MCD-00061")
        (field (name "MANUFACTURER_PART_NUMBER") "RC0402FR-071KL")
        (field (name "PROVIDED_BY") "SUBCO")
      )
      (libsource (lib "MCD_PARTS_database") (part "Resistor"))
    )
    (comp (ref "U2")
      (value "NT5CC256M16ER-EK")
      (footprint "ICC_VFBGA96_9x13_P080")
      (description "Memory,DDR3L,4Gb,256Mbx16,933Mhz,1V35,TFBGA")
      (fields
        (field (name "INTERNAL_PART_NUMBER") "MCD-01811")
        (field (name "MANUFACTURER") "NANYA")
        (field (name "PROVIDED_BY") "SUBCO")
      )
      (libsource (lib "MCD_PARTS_database") (part "NT5CC256M16ER-EK"))
    )
    (comp (ref "U6")
      (value "NT5CC256M16ER-EK")
      (footprint "ICC_VFBGA96_9x13_P080")
      (description "Memory,DDR3L,4Gb,256Mbx16,933Mhz,1V35,TFBGA")
      (fields
        (field (name "INTERNAL_PART_NUMBER") "MCD-01811")
        (field (name "MANUFACTURER") "NANYA")
        (field (name "PROVIDED_BY") "SUBCO")
      )
      (libsource (lib "MCD_PARTS_database") (part "NT5CC256M16ER-EK"))
    )
  )
  (nets
    (net (code "4") (name "/DDR_A0") (class "Default")
      (node (ref "R1") (pin "1") (pinfunction "1_1") (pintype "passive"))
      (node (ref "U2") (pin "N3") (pinfunction "A0_N3") (pintype "input"))
      (node (ref "U6") (pin "N3") (pinfunction "A0_N3") (pintype "input"))
    )
    (net (code "5") (name "/DDR_A1") (class "Default")
      (node (ref "R2") (pin "1") (pinfunction "1_1") (pintype "passive"))
      (node (ref "U2") (pin "P7") (pinfunction "A1_P7") (pintype "input"))
      (node (ref "U6") (pin "P7") (pinfunction "A1_P7") (pintype "input"))
    )
    (net (code "6") (name "/DDR_A2") (class "Default")
      (node (ref "R3") (pin "1") (pinfunction "1_1") (pintype "passive"))
      (node (ref "U2") (pin "P3") (pinfunction "A2_P3") (pintype "input"))
      (node (ref "U6") (pin "P3") (pinfunction "A2_P3") (pintype "input"))
    )
    (net (code "7") (name "/DDR_A3") (class "Default")
      (node (ref "R4") (pin "1") (pinfunction "1_1") (pintype "passive"))
      (node (ref "U2") (pin "N2") (pinfunction "A3_N2") (pintype "input"))
      (node (ref "U6") (pin "N2") (pinfunction "A3_N2") (pintype "input"))
    )
    (net (code "8") (name "/DDR_A4") (class "Default")
      (node (ref "R5") (pin "1") (pinfunction "1_1") (pintype "passive"))
      (node (ref "U2") (pin "P8") (pinfunction "A4_P8") (pintype "input"))
      (node (ref "U6") (pin "P8") (pinfunction "A4_P8") (pintype "input"))
    )
    (net (code "9") (name "/DDR_A5") (class "Default")
      (node (ref "R6") (pin "1") (pinfunction "1_1") (pintype "passive"))
      (node (ref "U2") (pin "P2") (pinfunction "A5_P2") (pintype "input"))
      (node (ref "U6") (pin "P2") (pinfunction "A5_P2") (pintype "input"))
    )
    (net (code "10") (name "/DDR_A6") (class "Default")
      (node (ref "R7") (pin "1") (pinfunction "1_1") (pintype "passive"))
      (node (ref "U2") (pin "R8") (pinfunction "A6_R8") (pintype "input"))
      (node (ref "U6") (pin "R8") (pinfunction "A6_R8") (pintype "input"))
    )
    (net (code "11") (name "/DDR_A7") (class "Default")
      (node (ref "R8") (pin "1") (pinfunction "1_1") (pintype "passive"))
      (node (ref "U2") (pin "R2") (pinfunction "A7_R2") (pintype "input"))
      (node (ref "U6") (pin "R2") (pinfunction "A7_R2") (pintype "input"))
    )
    (net (code "12") (name "/DDR_A8") (class "Default")
      (node (ref "R9") (pin "1") (pinfunction "1_1") (pintype "passive"))
      (node (ref "U2") (pin "T8") (pinfunction "A8_T8") (pintype "input"))
      (node (ref "U6") (pin "T8") (pinfunction "A8_T8") (pintype "input"))
    )
    (net (code "13") (name "/DDR_A9") (class "Default")
      (node (ref "R10") (pin "1") (pinfunction "1_1") (pintype "passive"))
      (node (ref "U2") (pin "R3") (pinfunction "A9_R3") (pintype "input"))
      (node (ref "U6") (pin "R3") (pinfunction "A9_R3") (pintype "input"))
    )
    (net (code "14") (name "/DDR_A10") (class "Default")
      (node (ref "R11") (pin "1") (pinfunction "1_1") (pintype "passive"))
      (node (ref "U2") (pin "L7") (pinfunction "A10/AP_L7") (pintype "input"))
      (node (ref "U6") (pin "L7") (pinfunction "A10/AP_L7") (pintype "input"))
    )
    (net (code "15") (name "/DDR_A11") (class "Default")
      (node (ref "R12") (pin "1") (pinfunction "1_1") (pintype "passive"))
      (node (ref "U2") (pin "R7") (pinfunction "A11_R7") (pintype "input"))
      (node (ref "U6") (pin "R7") (pinfunction "A11_R7") (pintype "input"))
    )
    (net (code "16") (name "/DDR_A12") (class "Default")
      (node (ref "R13") (pin "1") (pinfunction "1_1") (pintype "passive"))
      (node (ref "U2") (pin "N7") (pinfunction "A12/BC#_N7") (pintype "input"))
      (node (ref "U6") (pin "N7") (pinfunction "A12/BC#_N7") (pintype "input"))
    )
    (net (code "17") (name "/DDR_A13") (class "Default")
      (node (ref "R15") (pin "1") (pinfunction "1_1") (pintype "passive"))
      (node (ref "U2") (pin "T3") (pinfunction "A13_T3") (pintype "input"))
      (node (ref "U6") (pin "T3") (pinfunction "A13_T3") (pintype "input"))
    )
    (net (code "18") (name "/DDR_A14") (class "Default")
      (node (ref "R16") (pin "1") (pinfunction "1_1") (pintype "passive"))
      (node (ref "U2") (pin "T7") (pinfunction "A14_T7") (pintype "input"))
      (node (ref "U6") (pin "T7") (pinfunction "A14_T7") (pintype "input"))
    )
    (net (code "19") (name "/DDR_BA0") (class "Default")
      (node (ref "R17") (pin "1") (pinfunction "1_1") (pintype "passive"))
      (node (ref "U2") (pin "M2") (pinfunction "BA0_M2") (pintype "input"))
      (node (ref "U6") (pin "M2") (pinfunction "BA0_M2") (pintype "input"))
    )
    (net (code "20") (name "/DDR_BA1") (class "Default")
      (node (ref "R18") (pin "1") (pinfunction "1_1") (pintype "passive"))
      (node (ref "U2") (pin "N8") (pinfunction "BA1_N8") (pintype "input"))
      (node (ref "U6") (pin "N8") (pinfunction "BA1_N8") (pintype "input"))
    )
    (net (code "21") (name "/DDR_BA2") (class "Default")
      (node (ref "R19") (pin "1") (pinfunction "1_1") (pintype "passive"))
      (node (ref "U2") (pin "M3") (pinfunction "BA2_M3") (pintype "input"))
      (node (ref "U6") (pin "M3") (pinfunction "BA2_M3") (pintype "input"))
    )
    (net (code "22") (name "/DDR_CASN") (class "Default")
      (node (ref "R21") (pin "1") (pinfunction "1_1") (pintype "passive"))
      (node (ref "U2") (pin "K3") (pinfunction "CAS#_K3") (pintype "input"))
      (node (ref "U6") (pin "K3") (pinfunction "CAS#_K3") (pintype "input"))
    )
    (net (code "23") (name "/DDR_CKE") (class "Default")
      (node (ref "R23") (pin "1") (pinfunction "1_1") (pintype "passive"))
      (node (ref "R26") (pin "2") (pinfunction "2_2") (pintype "passive"))
      (node (ref "U2") (pin "K9") (pinfunction "CKE_K9") (pintype "input"))
      (node (ref "U6") (pin "K9") (pinfunction "CKE_K9") (pintype "input"))
    )
    (net (code "24") (name "/DDR_CLK_N") (class "Default")
      (node (ref "R14") (pin "2") (pinfunction "2_2") (pintype "passive"))
      (node (ref "U2") (pin "K7") (pinfunction "CK#_K7") (pintype "input"))
      (node (ref "U6") (pin "K7") (pinfunction "CK#_K7") (pintype "input"))
    )
    (net (code "25") (name "/DDR_CLK_P") (class "Default")
      (node (ref "R14") (pin "1") (pinfunction "1_1") (pintype "passive"))
      (node (ref "U2") (pin "J7") (pinfunction "CK_J7") (pintype "input"))
      (node (ref "U6") (pin "J7") (pinfunction "CK_J7") (pintype "input"))
    )
    (net (code "26") (name "/DDR_CSN") (class "Default")
      (node (ref "R22") (pin "1") (pinfunction "1_1") (pintype "passive"))
      (node (ref "U2") (pin "L2") (pinfunction "CS#_L2") (pintype "input"))
      (node (ref "U6") (pin "L2") (pinfunction "CS#_L2") (pintype "input"))
    )
    (net (code "27") (name "/DDR_DQ0") (class "Default")
      (node (ref "U2") (pin "D7") (pinfunction "DQU0_D7") (pintype "bidirectional"))
    )
    (net (code "28") (name "/DDR_DQ1") (class "Default")
      (node (ref "U2") (pin "A7") (pinfunction "DQU4_A7") (pintype "bidirectional"))
    )
    (net (code "29") (name "/DDR_DQ2") (class "Default")
      (node (ref "U2") (pin "A3") (pinfunction "DQU7_A3") (pintype "bidirectional"))
    )
    (net (code "30") (name "/DDR_DQ3") (class "Default")
      (node (ref "U2") (pin "B8") (pinfunction "DQU6_B8") (pintype "bidirectional"))
    )
    (net (code "31") (name "/DDR_DQ4") (class "Default")
      (node (ref "U2") (pin "C3") (pinfunction "DQU1_C3") (pintype "bidirectional"))
    )
    (net (code "32") (name "/DDR_DQ5") (class "Default")
      (node (ref "U2") (pin "C2") (pinfunction "DQU3_C2") (pintype "bidirectional"))
    )
    (net (code "33") (name "/DDR_DQ6") (class "Default")
      (node (ref "U2") (pin "A2") (pinfunction "DQU5_A2") (pintype "bidirectional"))
    )
    (net (code "34") (name "/DDR_DQ7") (class "Default")
      (node (ref "U2") (pin "C8") (pinfunction "DQU2_C8") (pintype "bidirectional"))
    )
    (net (code "35") (name "/DDR_DQ8") (class "Default")
      (node (ref "U2") (pin "E3") (pinfunction "DQL0_E3") (pintype "bidirectional"))
    )
    (net (code "36") (name "/DDR_DQ9") (class "Default")
      (node (ref "U2") (pin "H3") (pinfunction "DQL4_H3") (pintype "bidirectional"))
    )
    (net (code "37") (name "/DDR_DQ10") (class "Default")
      (node (ref "U2") (pin "F2") (pinfunction "DQL2_F2") (pintype "bidirectional"))
    )
    (net (code "38") (name "/DDR_DQ11") (class "Default")
      (node (ref "U2") (pin "F7") (pinfunction "DQL1_F7") (pintype "bidirectional"))
    )
    (net (code "39") (name "/DDR_DQ12") (class "Default")
      (node (ref "U2") (pin "H7") (pinfunction "DQL7_H7") (pintype "bidirectional"))
    )
    (net (code "40") (name "/DDR_DQ13") (class "Default")
      (node (ref "U2") (pin "G2") (pinfunction "DQL6_G2") (pintype "bidirectional"))
    )
    (net (code "41") (name "/DDR_DQ14") (class "Default")
      (node (ref "U2") (pin "F8") (pinfunction "DQL3_F8") (pintype "bidirectional"))
    )
    (net (code "42") (name "/DDR_DQ15") (class "Default")
      (node (ref "U2") (pin "H8") (pinfunction "DQL5_H8") (pintype "bidirectional"))
    )
    (net (code "43") (name "/DDR_DQ16") (class "Default")
      (node (ref "U6") (pin "D7") (pinfunction "DQU0_D7") (pintype "bidirectional"))
    )
    (net (code "44") (name "/DDR_DQ17") (class "Default")
      (node (ref "U6") (pin "A2") (pinfunction "DQU5_A2") (pintype "bidirectional"))
    )
    (net (code "45") (name "/DDR_DQ18") (class "Default")
      (node (ref "U6") (pin "A3") (pinfunction "DQU7_A3") (pintype "bidirectional"))
    )
    (net (code "46") (name "/DDR_DQ19") (class "Default")
      (node (ref "U6") (pin "B8") (pinfunction "DQU6_B8") (pintype "bidirectional"))
    )
    (net (code "47") (name "/DDR_DQ20") (class "Default")
      (node (ref "U6") (pin "C8") (pinfunction "DQU2_C8") (pintype "bidirectional"))
    )
    (net (code "48") (name "/DDR_DQ21") (class "Default")
      (node (ref "U6") (pin "C3") (pinfunction "DQU1_C3") (pintype "bidirectional"))
    )
    (net (code "49") (name "/DDR_DQ22") (class "Default")
      (node (ref "U6") (pin "C2") (pinfunction "DQU3_C2") (pintype "bidirectional"))
    )
    (net (code "50") (name "/DDR_DQ23") (class "Default")
      (node (ref "U6") (pin "A7") (pinfunction "DQU4_A7") (pintype "bidirectional"))
    )
    (net (code "51") (name "/DDR_DQ24") (class "Default")
      (node (ref "U6") (pin "E3") (pinfunction "DQL0_E3") (pintype "bidirectional"))
    )
    (net (code "52") (name "/DDR_DQ25") (class "Default")
      (node (ref "U6") (pin "F2") (pinfunction "DQL2_F2") (pintype "bidirectional"))
    )
    (net (code "53") (name "/DDR_DQ26") (class "Default")
      (node (ref "U6") (pin "F8") (pinfunction "DQL3_F8") (pintype "bidirectional"))
    )
    (net (code "54") (name "/DDR_DQ27") (class "Default")
      (node (ref "U6") (pin "H8") (pinfunction "DQL5_H8") (pintype "bidirectional"))
    )
    (net (code "55") (name "/DDR_DQ28") (class "Default")
      (node (ref "U6") (pin "F7") (pinfunction "DQL1_F7") (pintype "bidirectional"))
    )
    (net (code "56") (name "/DDR_DQ29") (class "Default")
      (node (ref "U6") (pin "H7") (pinfunction "DQL7_H7") (pintype "bidirectional"))
    )
    (net (code "57") (name "/DDR_DQ30") (class "Default")
      (node (ref "U6") (pin "G2") (pinfunction "DQL6_G2") (pintype "bidirectional"))
    )
    (net (code "58") (name "/DDR_DQ31") (class "Default")
      (node (ref "U6") (pin "H3") (pinfunction "DQL4_H3") (pintype "bidirectional"))
    )
    (net (code "59") (name "/DDR_DQM0") (class "Default")
      (node (ref "U2") (pin "D3") (pinfunction "DMU_D3") (pintype "input"))
    )
    (net (code "60") (name "/DDR_DQM1") (class "Default")
      (node (ref "U2") (pin "E7") (pinfunction "DML_E7") (pintype "input"))
    )
    (net (code "61") (name "/DDR_DQM2") (class "Default")
      (node (ref "U6") (pin "D3") (pinfunction "DMU_D3") (pintype "input"))
    )
    (net (code "62") (name "/DDR_DQM3") (class "Default")
      (node (ref "U6") (pin "E7") (pinfunction "DML_E7") (pintype "input"))
    )
    (net (code "63") (name "/DDR_DQS0_N") (class "Default")
      (node (ref "U2") (pin "B7") (pinfunction "DQSU#_B7") (pintype "bidirectional"))
    )
    (net (code "64") (name "/DDR_DQS0_P") (class "Default")
      (node (ref "U2") (pin "C7") (pinfunction "DQSU_C7") (pintype "bidirectional"))
    )
    (net (code "65") (name "/DDR_DQS1_N") (class "Default")
      (node (ref "U2") (pin "G3") (pinfunction "DQSL#_G3") (pintype "bidirectional"))
    )
    (net (code "66") (name "/DDR_DQS1_P") (class "Default")
      (node (ref "U2") (pin "F3") (pinfunction "DQSL_F3") (pintype "bidirectional"))
    )
    (net (code "67") (name "/DDR_DQS2_N") (class "Default")
      (node (ref "U6") (pin "B7") (pinfunction "DQSU#_B7") (pintype "bidirectional"))
    )
    (net (code "68") (name "/DDR_DQS2_P") (class "Default")
      (node (ref "U6") (pin "C7") (pinfunction "DQSU_C7") (pintype "bidirectional"))
    )
    (net (code "69") (name "/DDR_DQS3_N") (class "Default")
      (node (ref "U6") (pin "G3") (pinfunction "DQSL#_G3") (pintype "bidirectional"))
    )
    (net (code "70") (name "/DDR_DQS3_P") (class "Default")
      (node (ref "U6") (pin "F3") (pinfunction "DQSL_F3") (pintype "bidirectional"))
    )
    (net (code "71") (name "/DDR_ODT") (class "Default")
      (node (ref "R25") (pin "1") (pinfunction "1_1") (pintype "passive"))
      (node (ref "U2") (pin "K1") (pinfunction "ODT_K1") (pintype "input"))
      (node (ref "U6") (pin "K1") (pinfunction "ODT_K1") (pintype "input"))
    )
    (net (code "72") (name "/DDR_RASN") (class "Default")
      (node (ref "R20") (pin "1") (pinfunction "1_1") (pintype "passive"))
      (node (ref "U2") (pin "J3") (pinfunction "RAS#_J3") (pintype "input"))
      (node (ref "U6") (pin "J3") (pinfunction "RAS#_J3") (pintype "input"))
    )
    (net (code "73") (name "/DDR_RESETN") (class "Default")
      (node (ref "R28") (pin "2") (pinfunction "2_2") (pintype "passive"))
      (node (ref "U2") (pin "T2") (pinfunction "RESET#_T2") (pintype "input"))
      (node (ref "U6") (pin "T2") (pinfunction "RESET#_T2") (pintype "input"))
    )
    (net (code "74") (name "/DDR_WEN") (class "Default")
      (node (ref "R24") (pin "1") (pinfunction "1_1") (pintype "passive"))
      (node (ref "U2") (pin "L3") (pinfunction "WE#_L3") (pintype "input"))
      (node (ref "U6") (pin "L3") (pinfunction "WE#_L3") (pintype "input"))
    )
    (net (code "78") (name "GND") (class "Default")
      (node (ref "C1") (pin "2") (pinfunction "2_2") (pintype "passive"))
      (node (ref "C10") (pin "2") (pinfunction "2_2") (pintype "passive"))
      (node (ref "C11") (pin "2") (pinfunction "2_2") (pintype "passive"))
      (node (ref "C12") (pin "2") (pinfunction "2_2") (pintype "passive"))
      (node (ref "C13") (pin "1") (pinfunction "1_1") (pintype "passive"))
      (node (ref "C14") (pin "1") (pinfunction "1_1") (pintype "passive"))
      (node (ref "C15") (pin "1") (pinfunction "1_1") (pintype "passive"))
      (node (ref "C16") (pin "1") (pinfunction "1_1") (pintype "passive"))
      (node (ref "C17") (pin "2") (pinfunction "2_2") (pintype "passive"))
      (node (ref "C19") (pin "2") (pinfunction "2_2") (pintype "passive"))
      (node (ref "C2") (pin "2") (pinfunction "2_2") (pintype "passive"))
      (node (ref "C20") (pin "2") (pinfunction "2_2") (pintype "passive"))
      (node (ref "C21") (pin "2") (pinfunction "2_2") (pintype "passive"))
      (node (ref "C22") (pin "2") (pinfunction "2_2") (pintype "passive"))
      (node (ref "C23") (pin "2") (pinfunction "2_2") (pintype "passive"))
      (node (ref "C24") (pin "2") (pinfunction "2_2") (pintype "passive"))
      (node (ref "C25") (pin "2") (pinfunction "2_2") (pintype "passive"))
      (node (ref "C26") (pin "2") (pinfunction "2_2") (pintype "passive"))
      (node (ref "C27") (pin "2") (pinfunction "2_2") (pintype "passive"))
      (node (ref "C28") (pin "2") (pinfunction "2_2") (pintype "passive"))
      (node (ref "C3") (pin "2") (pinfunction "2_2") (pintype "passive"))
      (node (ref "C4") (pin "2") (pinfunction "2_2") (pintype "passive"))
      (node (ref "C5") (pin "2") (pinfunction "2_2") (pintype "passive"))
      (node (ref "C58") (pin "1") (pinfunction "1_1") (pintype "passive"))
      (node (ref "C59") (pin "1") (pinfunction "1_1") (pintype "passive"))
      (node (ref "C6") (pin "2") (pinfunction "2_2") (pintype "passive"))
      (node (ref "C60") (pin "2") (pinfunction "2_2") (pintype "passive"))
      (node (ref "C62") (pin "2") (pinfunction "2_2") (pintype "passive"))
      (node (ref "C63") (pin "2") (pinfunction "2_2") (pintype "passive"))
      (node (ref "C64") (pin "2") (pinfunction "2_2") (pintype "passive"))
      (node (ref "C65") (pin "2") (pinfunction "2_2") (pintype "passive"))
      (node (ref "C7") (pin "2") (pinfunction "2_2") (pintype "passive"))
      (node (ref "C73") (pin "2") (pinfunction "2_2") (pintype "passive"))
      (node (ref "C74") (pin "2") (pinfunction "2_2") (pintype "passive"))
      (node (ref "C8") (pin "2") (pinfunction "2_2") (pintype "passive"))
      (node (ref "C84") (pin "2") (pinfunction "2_2") (pintype "passive"))
      (node (ref "C85") (pin "2") (pinfunction "2_2") (pintype "passive"))
      (node (ref "C86") (pin "2") (pinfunction "2_2") (pintype "passive"))
      (node (ref "C87") (pin "2") (pinfunction "2_2") (pintype "passive"))
      (node (ref "C89") (pin "2") (pinfunction "2_2") (pintype "passive"))
      (node (ref "C9") (pin "2") (pinfunction "2_2") (pintype "passive"))
      (node (ref "C90") (pin "2") (pinfunction "2_2") (pintype "passive"))
      (node (ref "C91") (pin "2") (pinfunction "2_2") (pintype "passive"))
      (node (ref "C93") (pin "2") (pinfunction "2_2") (pintype "passive"))
      (node (ref "R26") (pin "1") (pinfunction "1_1") (pintype "passive"))
      (node (ref "R28") (pin "1") (pinfunction "1_1") (pintype "passive"))
      (node (ref "R29") (pin "1") (pinfunction "1_1") (pintype "passive"))
      (node (ref "R30") (pin "1") (pinfunction "1_1") (pintype "passive"))
      (node (ref "R42") (pin "1") (pinfunction "1_1") (pintype "passive"))
      (node (ref "R44") (pin "1") (pinfunction "1_1") (pintype "passive"))
      (node (ref "R45") (pin "1") (pinfunction "1_1") (pintype "passive"))
      (node (ref "R46") (pin "1") (pinfunction "1_1") (pintype "passive"))
      (node (ref "U2") (pin "A9") (pinfunction "VSS_A9") (pintype "power_in"))
      (node (ref "U2") (pin "B1") (pinfunction "VSSQ_B1") (pintype "power_in"))
      (node (ref "U2") (pin "B3") (pinfunction "VSS_B3") (pintype "power_in"))
      (node (ref "U2") (pin "B9") (pinfunction "VSSQ_B9") (pintype "power_in"))
      (node (ref "U2") (pin "D1") (pinfunction "VSSQ_D1") (pintype "power_in"))
      (node (ref "U2") (pin "D8") (pinfunction "VSSQ_D8") (pintype "power_in"))
      (node (ref "U2") (pin "E1") (pinfunction "VSS_E1") (pintype "power_in"))
      (node (ref "U2") (pin "E2") (pinfunction "VSSQ_E2") (pintype "power_in"))
      (node (ref "U2") (pin "E8") (pinfunction "VSSQ_E8") (pintype "power_in"))
      (node (ref "U2") (pin "F9") (pinfunction "VSSQ_F9") (pintype "power_in"))
      (node (ref "U2") (pin "G1") (pinfunction "VSSQ_G1") (pintype "power_in"))
      (node (ref "U2") (pin "G8") (pinfunction "VSS_G8") (pintype "power_in"))
      (node (ref "U2") (pin "G9") (pinfunction "VSSQ_G9") (pintype "power_in"))
      (node (ref "U2") (pin "J2") (pinfunction "VSS_J2") (pintype "power_in"))
      (node (ref "U2") (pin "J8") (pinfunction "VSS_J8") (pintype "power_in"))
      (node (ref "U2") (pin "M1") (pinfunction "VSS_M1") (pintype "power_in"))
      (node (ref "U2") (pin "M9") (pinfunction "VSS_M9") (pintype "power_in"))
      (node (ref "U2") (pin "P1") (pinfunction "VSS_P1") (pintype "power_in"))
      (node (ref "U2") (pin "P9") (pinfunction "VSS_P9") (pintype "power_in"))
      (node (ref "U2") (pin "T1") (pinfunction "VSS_T1") (pintype "power_in"))
      (node (ref "U2") (pin "T9") (pinfunction "VSS_T9") (pintype "power_in"))
      (node (ref "U6") (pin "A9") (pinfunction "VSS_A9") (pintype "power_in"))
      (node (ref "U6") (pin "B1") (pinfunction "VSSQ_B1") (pintype "power_in"))
      (node (ref "U6") (pin "B3") (pinfunction "VSS_B3") (pintype "power_in"))
      (node (ref "U6") (pin "B9") (pinfunction "VSSQ_B9") (pintype "power_in"))
      (node (ref "U6") (pin "D1") (pinfunction "VSSQ_D1") (pintype "power_in"))
      (node (ref "U6") (pin "D8") (pinfunction "VSSQ_D8") (pintype "power_in"))
      (node (ref "U6") (pin "E1") (pinfunction "VSS_E1") (pintype "power_in"))
      (node (ref "U6") (pin "E2") (pinfunction "VSSQ_E2") (pintype "power_in"))
      (node (ref "U6") (pin "E8") (pinfunction "VSSQ_E8") (pintype "power_in"))
      (node (ref "U6") (pin "F9") (pinfunction "VSSQ_F9") (pintype "power_in"))
      (node (ref "U6") (pin "G1") (pinfunction "VSSQ_G1") (pintype "power_in"))
      (node (ref "U6") (pin "G8") (pinfunction "VSS_G8") (pintype "power_in"))
      (node (ref "U6") (pin "G9") (pinfunction "VSSQ_G9") (pintype "power_in"))
      (node (ref "U6") (pin "J2") (pinfunction "VSS_J2") (pintype "power_in"))
      (node (ref "U6") (pin "J8") (pinfunction "VSS_J8") (pintype "power_in"))
      (node (ref "U6") (pin "M1") (pinfunction "VSS_M1") (pintype "power_in"))
      (node (ref "U6") (pin "M9") (pinfunction "VSS_M9") (pintype "power_in"))
      (node (ref "U6") (pin "P1") (pinfunction "VSS_P1") (pintype "power_in"))
      (node (ref "U6") (pin "P9") (pinfunction "VSS_P9") (pintype "power_in"))
      (node (ref "U6") (pin "T1") (pinfunction "VSS_T1") (pintype "power_in"))
      (node (ref "U6") (pin "T9") (pinfunction "VSS_T9") (pintype "power_in"))
    )
    (net (code "79") (name "Net-(U2-VREFCA)") (class "Default")
      (node (ref "C26") (pin "1") (pinfunction "1_1") (pintype "passive"))
      (node (ref "R34") (pin "1") (pinfunction "1_1") (pintype "passive"))
      (node (ref "R44") (pin "2") (pinfunction "2_2") (pintype "passive"))
      (node (ref "U2") (pin "M8") (pinfunction "VREFCA_M8") (pintype "passive"))
    )
    (net (code "80") (name "Net-(U2-VREFDQ)") (class "Default")
      (node (ref "C25") (pin "1") (pinfunction "1_1") (pintype "passive"))
      (node (ref "R33") (pin "1") (pinfunction "1_1") (pintype "passive"))
      (node (ref "R42") (pin "2") (pinfunction "2_2") (pintype "passive"))
      (node (ref "U2") (pin "H1") (pinfunction "VREFDQ_H1") (pintype "passive"))
    )
    (net (code "81") (name "Net-(U2-ZQ)") (class "Default")
      (node (ref "R29") (pin "2") (pinfunction "2_2") (pintype "passive"))
      (node (ref "U2") (pin "L8") (pinfunction "ZQ_L8") (pintype "passive"))
    )
    (net (code "82") (name "Net-(U6-VREFCA)") (class "Default")
      (node (ref "C28") (pin "1") (pinfunction "1_1") (pintype "passive"))
      (node (ref "R36") (pin "1") (pinfunction "1_1") (pintype "passive"))
      (node (ref "R46") (pin "2") (pinfunction "2_2") (pintype "passive"))
      (node (ref "U6") (pin "M8") (pinfunction "VREFCA_M8") (pintype "passive"))
    )
    (net (code "83") (name "Net-(U6-VREFDQ)") (class "Default")
      (node (ref "C27") (pin "1") (pinfunction "1_1") (pintype "passive"))
      (node (ref "R35") (pin "1") (pinfunction "1_1") (pintype "passive"))
      (node (ref "R45") (pin "2") (pinfunction "2_2") (pintype "passive"))
      (node (ref "U6") (pin "H1") (pinfunction "VREFDQ_H1") (pintype "passive"))
    )
    (net (code "84") (name "Net-(U6-ZQ)") (class "Default")
      (node (ref "R30") (pin "2") (pinfunction "2_2") (pintype "passive"))
      (node (ref "U6") (pin "L8") (pinfunction "ZQ_L8") (pintype "passive"))
    )
    (net (code "85") (name "VDD_DDR") (class "Default")
      (node (ref "C15") (pin "2") (pinfunction "2_2") (pintype "passive"))
      (node (ref "C16") (pin "2") (pinfunction "2_2") (pintype "passive"))
      (node (ref "C17") (pin "1") (pinfunction "1_1") (pintype "passive"))
      (node (ref "C19") (pin "1") (pinfunction "1_1") (pintype "passive"))
      (node (ref "C20") (pin "1") (pinfunction "1_1") (pintype "passive"))
      (node (ref "C21") (pin "1") (pinfunction "1_1") (pintype "passive"))
      (node (ref "C22") (pin "1") (pinfunction "1_1") (pintype "passive"))
      (node (ref "C23") (pin "1") (pinfunction "1_1") (pintype "passive"))
      (node (ref "C24") (pin "1") (pinfunction "1_1") (pintype "passive"))
      (node (ref "C58") (pin "2") (pinfunction "2_2") (pintype "passive"))
      (node (ref "C59") (pin "2") (pinfunction "2_2") (pintype "passive"))
      (node (ref "C60") (pin "1") (pinfunction "1_1") (pintype "passive"))
      (node (ref "C62") (pin "1") (pinfunction "1_1") (pintype "passive"))
      (node (ref "C63") (pin "1") (pinfunction "1_1") (pintype "passive"))
      (node (ref "C64") (pin "1") (pinfunction "1_1") (pintype "passive"))
      (node (ref "C65") (pin "1") (pinfunction "1_1") (pintype "passive"))
      (node (ref "C73") (pin "1") (pinfunction "1_1") (pintype "passive"))
      (node (ref "C74") (pin "1") (pinfunction "1_1") (pintype "passive"))
      (node (ref "C84") (pin "1") (pinfunction "1_1") (pintype "passive"))
      (node (ref "C85") (pin "1") (pinfunction "1_1") (pintype "passive"))
      (node (ref "C86") (pin "1") (pinfunction "1_1") (pintype "passive"))
      (node (ref "C87") (pin "1") (pinfunction "1_1") (pintype "passive"))
      (node (ref "C89") (pin "1") (pinfunction "1_1") (pintype "passive"))
      (node (ref "C90") (pin "1") (pinfunction "1_1") (pintype "passive"))
      (node (ref "C91") (pin "1") (pinfunction "1_1") (pintype "passive"))
      (node (ref "C93") (pin "1") (pinfunction "1_1") (pintype "passive"))
      (node (ref "R33") (pin "2") (pinfunction "2_2") (pintype "passive"))
      (node (ref "R34") (pin "2") (pinfunction "2_2") (pintype "passive"))
      (node (ref "R35") (pin "2") (pinfunction "2_2") (pintype "passive"))
      (node (ref "R36") (pin "2") (pinfunction "2_2") (pintype "passive"))
      (node (ref "U2") (pin "A1") (pinfunction "VDDQ_A1") (pintype "power_in"))
      (node (ref "U2") (pin "A8") (pinfunction "VDDQ_A8") (pintype "power_in"))
      (node (ref "U2") (pin "B2") (pinfunction "VDD_B2") (pintype "power_in"))
      (node (ref "U2") (pin "C1") (pinfunction "VDDQ_C1") (pintype "power_in"))
      (node (ref "U2") (pin "C9") (pinfunction "VDDQ_C9") (pintype "power_in"))
      (node (ref "U2") (pin "D2") (pinfunction "VDDQ_D2") (pintype "power_in"))
      (node (ref "U2") (pin "D9") (pinfunction "VDD_D9") (pintype "power_in"))
      (node (ref "U2") (pin "E9") (pinfunction "VDDQ_E9") (pintype "power_in"))
      (node (ref "U2") (pin "F1") (pinfunction "VDDQ_F1") (pintype "power_in"))
      (node (ref "U2") (pin "G7") (pinfunction "VDD_G7") (pintype "power_in"))
      (node (ref "U2") (pin "H2") (pinfunction "VDDQ_H2") (pintype "power_in"))
      (node (ref "U2") (pin "H9") (pinfunction "VDDQ_H9") (pintype "power_in"))
      (node (ref "U2") (pin "K2") (pinfunction "VDD_K2") (pintype "power_in"))
      (node (ref "U2") (pin "K8") (pinfunction "VDD_K8") (pintype "power_in"))
      (node (ref "U2") (pin "N1") (pinfunction "VDD_N1") (pintype "power_in"))
      (node (ref "U2") (pin "N9") (pinfunction "VDD_N9") (pintype "power_in"))
      (node (ref "U2") (pin "R1") (pinfunction "VDD_R1") (pintype "power_in"))
      (node (ref "U2") (pin "R9") (pinfunction "VDD_R9") (pintype "power_in"))
      (node (ref "U6") (pin "A1") (pinfunction "VDDQ_A1") (pintype "power_in"))
      (node (ref "U6") (pin "A8") (pinfunction "VDDQ_A8") (pintype "power_in"))
      (node (ref "U6") (pin "B2") (pinfunction "VDD_B2") (pintype "power_in"))
      (node (ref "U6") (pin "C1") (pinfunction "VDDQ_C1") (pintype "power_in"))
      (node (ref "U6") (pin "C9") (pinfunction "VDDQ_C9") (pintype "power_in"))
      (node (ref "U6") (pin "D2") (pinfunction "VDDQ_D2") (pintype "power_in"))
      (node (ref "U6") (pin "D9") (pinfunction "VDD_D9") (pintype "power_in"))
      (node (ref "U6") (pin "E9") (pinfunction "VDDQ_E9") (pintype "power_in"))
      (node (ref "U6") (pin "F1") (pinfunction "VDDQ_F1") (pintype "power_in"))
      (node (ref "U6") (pin "G7") (pinfunction "VDD_G7") (pintype "power_in"))
      (node (ref "U6") (pin "H2") (pinfunction "VDDQ_H2") (pintype "power_in"))
      (node (ref "U6") (pin "H9") (pinfunction "VDDQ_H9") (pintype "power_in"))
      (node (ref "U6") (pin "K2") (pinfunction "VDD_K2") (pintype "power_in"))
      (node (ref "U6") (pin "K8") (pinfunction "VDD_K8") (pintype "power_in"))
      (node (ref "U6") (pin "N1") (pinfunction "VDD_N1") (pintype "power_in"))
      (node (ref "U6") (pin "N9") (pinfunction "VDD_N9") (pintype "power_in"))
      (node (ref "U6") (pin "R1") (pinfunction "VDD_R1") (pintype "power_in"))
      (node (ref "U6") (pin "R9") (pinfunction "VDD_R9") (pintype "power_in"))
    )
    (net (code "86") (name "VTT_DDR") (class "Default")
      (node (ref "C1") (pin "1") (pinfunction "1_1") (pintype "passive"))
      (node (ref "C10") (pin "1") (pinfunction "1_1") (pintype "passive"))
      (node (ref "C11") (pin "1") (pinfunction "1_1") (pintype "passive"))
      (node (ref "C12") (pin "1") (pinfunction "1_1") (pintype "passive"))
      (node (ref "C13") (pin "2") (pinfunction "2_2") (pintype "passive"))
      (node (ref "C14") (pin "2") (pinfunction "2_2") (pintype "passive"))
      (node (ref "C2") (pin "1") (pinfunction "1_1") (pintype "passive"))
      (node (ref "C3") (pin "1") (pinfunction "1_1") (pintype "passive"))
      (node (ref "C4") (pin "1") (pinfunction "1_1") (pintype "passive"))
      (node (ref "C5") (pin "1") (pinfunction "1_1") (pintype "passive"))
      (node (ref "C6") (pin "1") (pinfunction "1_1") (pintype "passive"))
      (node (ref "C7") (pin "1") (pinfunction "1_1") (pintype "passive"))
      (node (ref "C8") (pin "1") (pinfunction "1_1") (pintype "passive"))
      (node (ref "C9") (pin "1") (pinfunction "1_1") (pintype "passive"))
      (node (ref "R1") (pin "2") (pinfunction "2_2") (pintype "passive"))
      (node (ref "R10") (pin "2") (pinfunction "2_2") (pintype "passive"))
      (node (ref "R11") (pin "2") (pinfunction "2_2") (pintype "passive"))
      (node (ref "R12") (pin "2") (pinfunction "2_2") (pintype "passive"))
      (node (ref "R13") (pin "2") (pinfunction "2_2") (pintype "passive"))
      (node (ref "R15") (pin "2") (pinfunction "2_2") (pintype "passive"))
      (node (ref "R16") (pin "2") (pinfunction "2_2") (pintype "passive"))
      (node (ref "R17") (pin "2") (pinfunction "2_2") (pintype "passive"))
      (node (ref "R18") (pin "2") (pinfunction "2_2") (pintype "passive"))
      (node (ref "R19") (pin "2") (pinfunction "2_2") (pintype "passive"))
      (node (ref "R2") (pin "2") (pinfunction "2_2") (pintype "passive"))
      (node (ref "R20") (pin "2") (pinfunction "2_2") (pintype "passive"))
      (node (ref "R21") (pin "2") (pinfunction "2_2") (pintype "passive"))
      (node (ref "R22") (pin "2") (pinfunction "2_2") (pintype "passive"))
      (node (ref "R23") (pin "2") (pinfunction "2_2") (pintype "passive"))
      (node (ref "R24") (pin "2") (pinfunction "2_2") (pintype "passive"))
      (node (ref "R25") (pin "2") (pinfunction "2_2") (pintype "passive"))
      (node (ref "R3") (pin "2") (pinfunction "2_2") (pintype "passive"))
      (node (ref "R4") (pin "2") (pinfunction "2_2") (pintype "passive"))
      (node (ref "R5") (pin "2") (pinfunction "2_2") (pintype "passive"))
      (node (ref "R6") (pin "2") (pinfunction "2_2") (pintype "passive"))
      (node (ref "R7") (pin "2") (pinfunction "2_2") (pintype "passive"))
      (node (ref "R8") (pin "2") (pinfunction "2_2") (pintype "passive"))
      (node (ref "R9") (pin "2") (pinfunction "2_2") (pintype "passive"))
    )
    (net (code "87") (name "unconnected-(U2-A15-PadM7)") (class "Default")
      (node (ref "U2") (pin "M7") (pinfunction "A15_M7") (pintype "input+no_connect"))
    )
    (net (code "88") (name "unconnected-(U2-NC-PadJ1)") (class "Default")
      (node (ref "U2") (pin "J1") (pinfunction "NC_J1") (pintype "passive+no_connect"))
    )
    (net (code "89") (name "unconnected-(U2-NC-PadJ9)") (class "Default")
      (node (ref "U2") (pin "J9") (pinfunction "NC_J9") (pintype "passive+no_connect"))
    )
    (net (code "90") (name "unconnected-(U2-NC-PadL1)") (class "Default")
      (node (ref "U2") (pin "L1") (pinfunction "NC_L1") (pintype "passive+no_connect"))
    )
    (net (code "91") (name "unconnected-(U2-NC-PadL9)") (class "Default")
      (node (ref "U2") (pin "L9") (pinfunction "NC_L9") (pintype "passive+no_connect"))
    )
    (net (code "92") (name "unconnected-(U6-A15-PadM7)") (class "Default")
      (node (ref "U6") (pin "M7") (pinfunction "A15_M7") (pintype "input+no_connect"))
    )
    (net (code "93") (name "unconnected-(U6-NC-PadJ1)") (class "Default")
      (node (ref "U6") (pin "J1") (pinfunction "NC_J1") (pintype "passive+no_connect"))
    )
    (net (code "94") (name "unconnected-(U6-NC-PadJ9)") (class "Default")
      (node (ref "U6") (pin "J9") (pinfunction "NC_J9") (pintype "passive+no_connect"))
    )
    (net (code "95") (name "unconnected-(U6-NC-PadL1)") (class "Default")
      (node (ref "U6") (pin "L1") (pinfunction "NC_L1") (pintype "passive+no_connect"))
    )
    (net (code "96") (name "unconnected-(U6-NC-PadL9)") (class "Default")
      (node (ref "U6") (pin "L9") (pinfunction "NC_L9") (pintype "passive+no_connect"))
    )
  )
)
